# propulsion_alim.net
KiCad netlist of a schematic drawn in Altium Designer
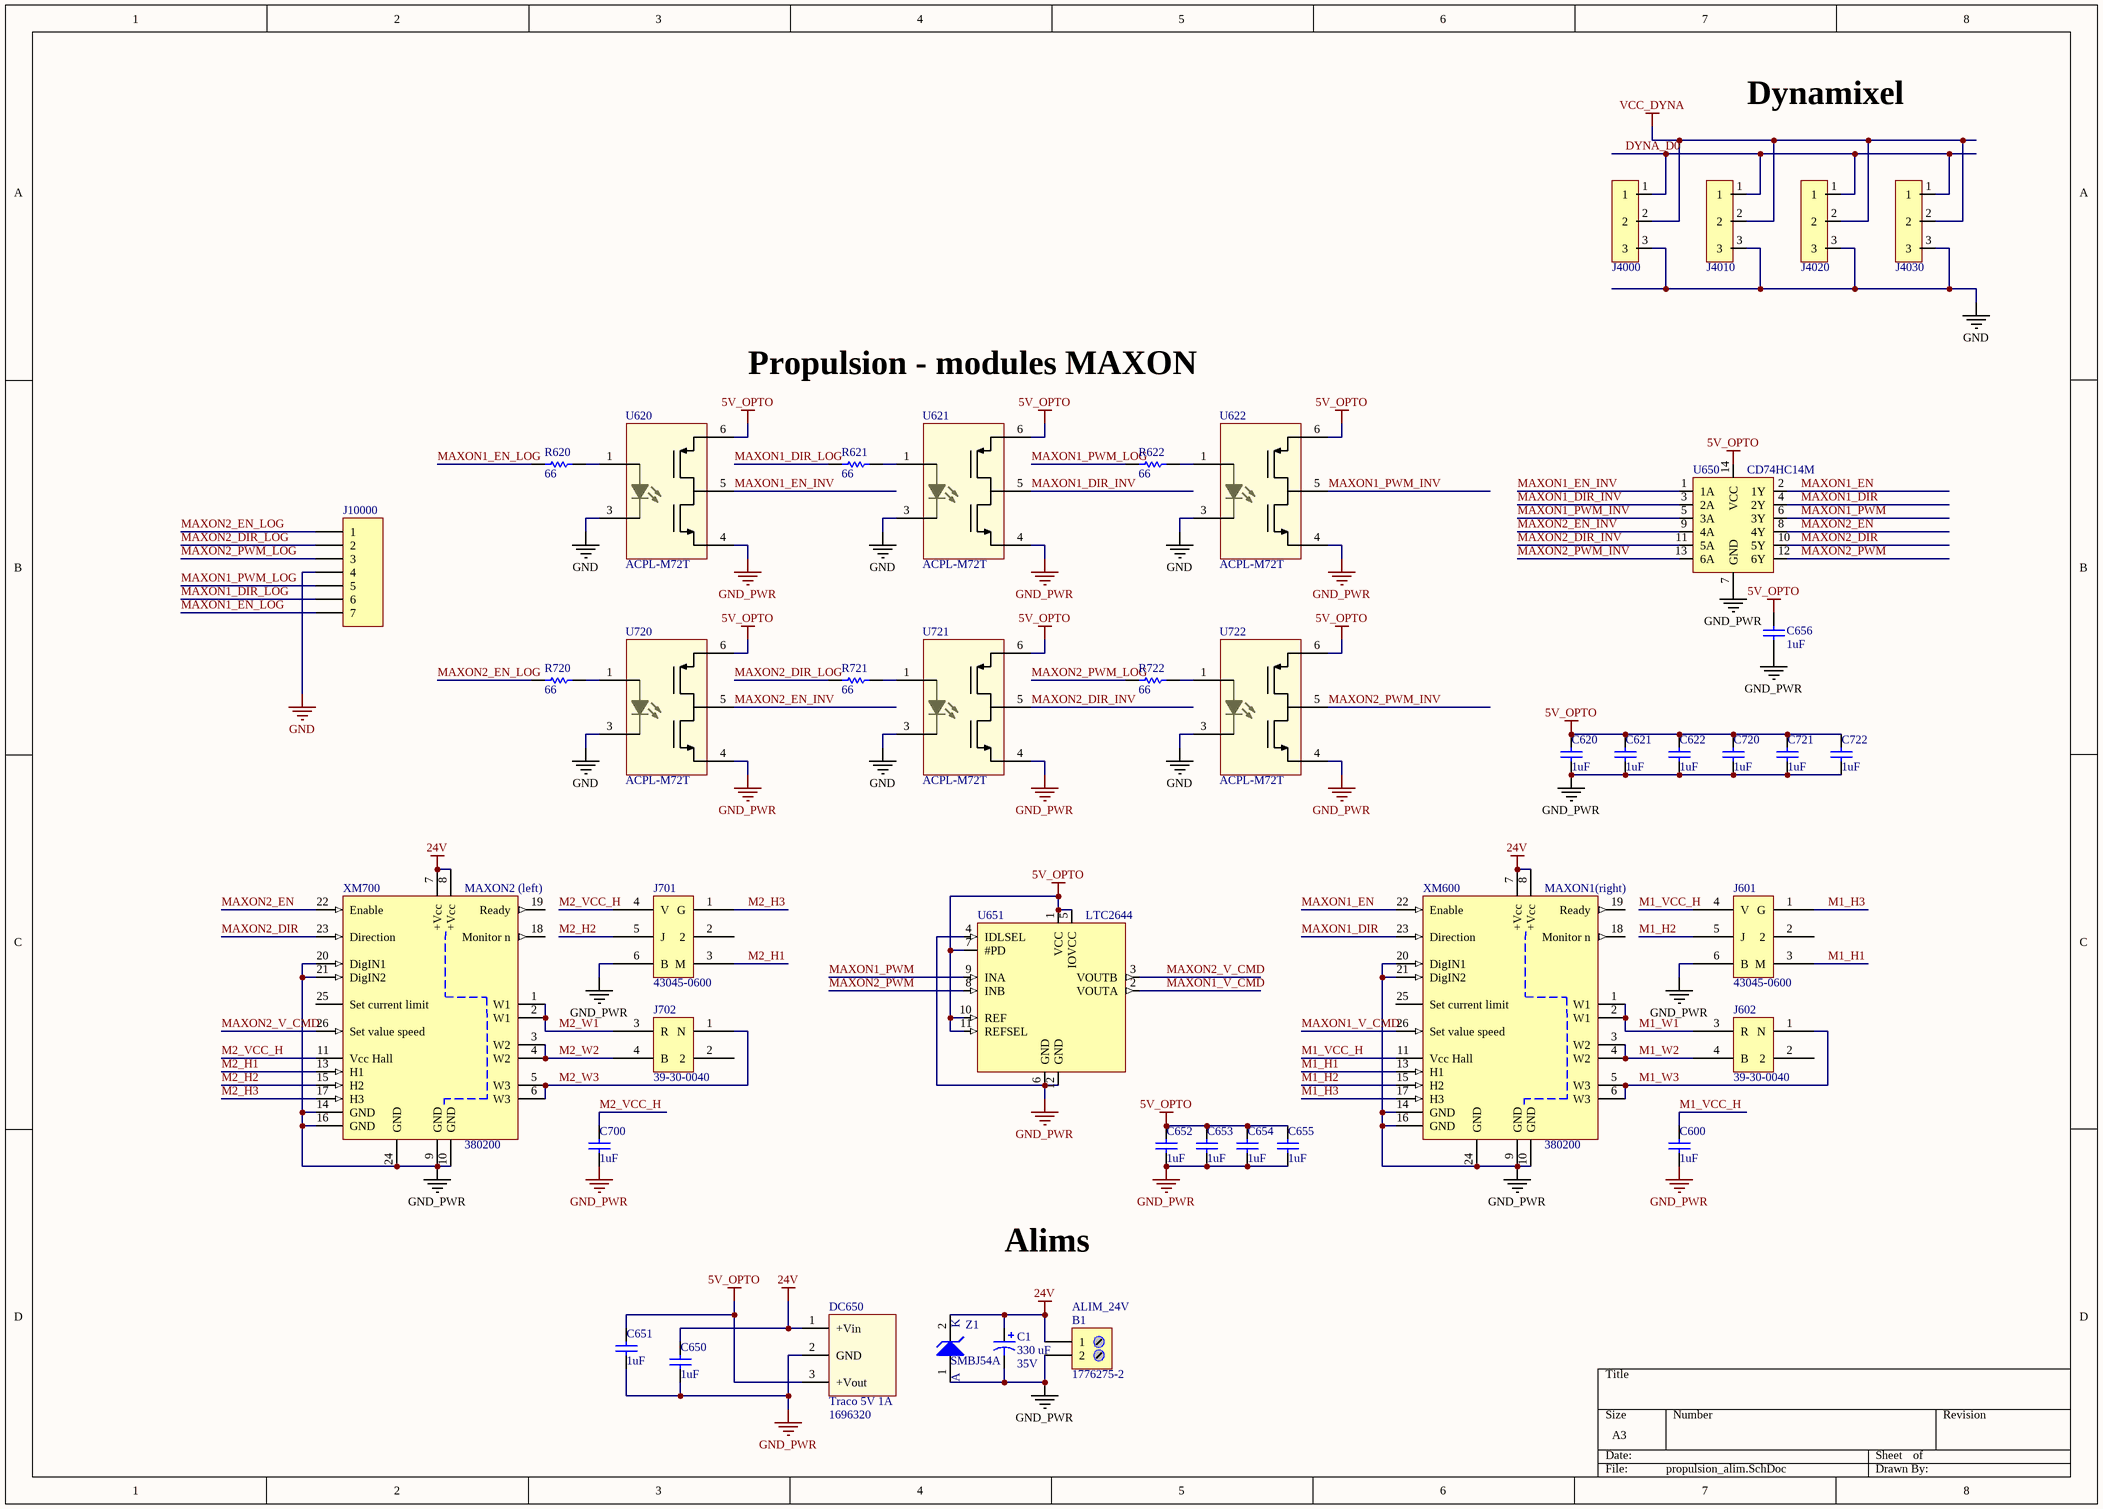
[diagram p0: propulsion_alim.SchDoc]

(export (version "E")
  (design (tool "Eeschema 10.0.6"))
  (components
    (comp (ref "B1")
      (value "1776275-2")
      (footprint "BORNIER_2V_3.5MM")
      (description "TERM BLOCK 2POS SIDE ENT 3.5MM")
      (fields (field (name "MANUFACTURER") "TE Connectivity AMP Connectors"))
      (libsource (lib "Divers") (part "1776275-2"))
    )
    (comp (ref "C1")
      (value "330 uF")
      (footprint "WCAP-ATG8_10x12.5x5x0.6")
      (description "CAP Alu 330 UF 20% 35 V")
      (fields
        (field (name "MANUFACTURER") "Wurth Elektronik")
        (field (name "MANUFACTURER PART NUMBER") "860010575012")
        (field (name "RATEDVOLTAGE") "35V")
      )
      (libsource (lib "Condensateur") (part "WCAP-ATG8, 860010575012"))
    )
    (comp (ref "C600")
      (value "1uF")
      (footprint "WCAP-CSGP_0805, 2x1.25x1.25")
      (description "CAP CER 1uF 50V X7R 0805")
      (fields
        (field (name "MANUFACTURER") "Wurth Elektronik")
        (field (name "MANUFACTURER PART NUMBER") "885012207103")
      )
      (libsource (lib "Condensateur") (part "WCAP-CSGP, 885012207103"))
    )
    (comp (ref "C620")
      (value "1uF")
      (footprint "WCAP-CSGP_0805, 2x1.25x1.25")
      (description "CAP CER 1uF 50V X7R 0805")
      (fields
        (field (name "MANUFACTURER") "Wurth Elektronik")
        (field (name "MANUFACTURER PART NUMBER") "885012207103")
      )
      (libsource (lib "Condensateur") (part "WCAP-CSGP, 885012207103"))
    )
    (comp (ref "C621")
      (value "1uF")
      (footprint "WCAP-CSGP_0805, 2x1.25x1.25")
      (description "CAP CER 1uF 50V X7R 0805")
      (fields
        (field (name "MANUFACTURER") "Wurth Elektronik")
        (field (name "MANUFACTURER PART NUMBER") "885012207103")
      )
      (libsource (lib "Condensateur") (part "WCAP-CSGP, 885012207103"))
    )
    (comp (ref "C622")
      (value "1uF")
      (footprint "WCAP-CSGP_0805, 2x1.25x1.25")
      (description "CAP CER 1uF 50V X7R 0805")
      (fields
        (field (name "MANUFACTURER") "Wurth Elektronik")
        (field (name "MANUFACTURER PART NUMBER") "885012207103")
      )
      (libsource (lib "Condensateur") (part "WCAP-CSGP, 885012207103"))
    )
    (comp (ref "C650")
      (value "1uF")
      (footprint "WCAP-CSGP_0805, 2x1.25x1.25")
      (description "CAP CER 1uF 50V X7R 0805")
      (fields
        (field (name "MANUFACTURER") "Wurth Elektronik")
        (field (name "MANUFACTURER PART NUMBER") "885012207103")
      )
      (libsource (lib "Condensateur") (part "WCAP-CSGP, 885012207103"))
    )
    (comp (ref "C651")
      (value "1uF")
      (footprint "WCAP-CSGP_0805, 2x1.25x1.25")
      (description "CAP CER 1uF 50V X7R 0805")
      (fields
        (field (name "MANUFACTURER") "Wurth Elektronik")
        (field (name "MANUFACTURER PART NUMBER") "885012207103")
      )
      (libsource (lib "Condensateur") (part "WCAP-CSGP, 885012207103"))
    )
    (comp (ref "C652")
      (value "1uF")
      (footprint "WCAP-CSGP_0805, 2x1.25x1.25")
      (description "CAP CER 1uF 50V X7R 0805")
      (fields
        (field (name "MANUFACTURER") "Wurth Elektronik")
        (field (name "MANUFACTURER PART NUMBER") "885012207103")
      )
      (libsource (lib "Condensateur") (part "WCAP-CSGP, 885012207103"))
    )
    (comp (ref "C653")
      (value "1uF")
      (footprint "WCAP-CSGP_0805, 2x1.25x1.25")
      (description "CAP CER 1uF 50V X7R 0805")
      (fields
        (field (name "MANUFACTURER") "Wurth Elektronik")
        (field (name "MANUFACTURER PART NUMBER") "885012207103")
      )
      (libsource (lib "Condensateur") (part "WCAP-CSGP, 885012207103"))
    )
    (comp (ref "C654")
      (value "1uF")
      (footprint "WCAP-CSGP_0805, 2x1.25x1.25")
      (description "CAP CER 1uF 50V X7R 0805")
      (fields
        (field (name "MANUFACTURER") "Wurth Elektronik")
        (field (name "MANUFACTURER PART NUMBER") "885012207103")
      )
      (libsource (lib "Condensateur") (part "WCAP-CSGP, 885012207103"))
    )
    (comp (ref "C655")
      (value "1uF")
      (footprint "WCAP-CSGP_0805, 2x1.25x1.25")
      (description "CAP CER 1uF 50V X7R 0805")
      (fields
        (field (name "MANUFACTURER") "Wurth Elektronik")
        (field (name "MANUFACTURER PART NUMBER") "885012207103")
      )
      (libsource (lib "Condensateur") (part "WCAP-CSGP, 885012207103"))
    )
    (comp (ref "C656")
      (value "1uF")
      (footprint "WCAP-CSGP_0805, 2x1.25x1.25")
      (description "CAP CER 1uF 50V X7R 0805")
      (fields
        (field (name "MANUFACTURER") "Wurth Elektronik")
        (field (name "MANUFACTURER PART NUMBER") "885012207103")
      )
      (libsource (lib "Condensateur") (part "WCAP-CSGP, 885012207103"))
    )
    (comp (ref "C700")
      (value "1uF")
      (footprint "WCAP-CSGP_0805, 2x1.25x1.25")
      (description "CAP CER 1uF 50V X7R 0805")
      (fields
        (field (name "MANUFACTURER") "Wurth Elektronik")
        (field (name "MANUFACTURER PART NUMBER") "885012207103")
      )
      (libsource (lib "Condensateur") (part "WCAP-CSGP, 885012207103"))
    )
    (comp (ref "C720")
      (value "1uF")
      (footprint "WCAP-CSGP_0805, 2x1.25x1.25")
      (description "CAP CER 1uF 50V X7R 0805")
      (fields
        (field (name "MANUFACTURER") "Wurth Elektronik")
        (field (name "MANUFACTURER PART NUMBER") "885012207103")
      )
      (libsource (lib "Condensateur") (part "WCAP-CSGP, 885012207103"))
    )
    (comp (ref "C721")
      (value "1uF")
      (footprint "WCAP-CSGP_0805, 2x1.25x1.25")
      (description "CAP CER 1uF 50V X7R 0805")
      (fields
        (field (name "MANUFACTURER") "Wurth Elektronik")
        (field (name "MANUFACTURER PART NUMBER") "885012207103")
      )
      (libsource (lib "Condensateur") (part "WCAP-CSGP, 885012207103"))
    )
    (comp (ref "C722")
      (value "1uF")
      (footprint "WCAP-CSGP_0805, 2x1.25x1.25")
      (description "CAP CER 1uF 50V X7R 0805")
      (fields
        (field (name "MANUFACTURER") "Wurth Elektronik")
        (field (name "MANUFACTURER PART NUMBER") "885012207103")
      )
      (libsource (lib "Condensateur") (part "WCAP-CSGP, 885012207103"))
    )
    (comp (ref "DC650")
      (value "Traco 5V 1A")
      (footprint "TSR1")
      (description "Traco 12.0V 12W 1A")
      (fields
        (field (name "MANUFACTURER") "TRACOPOWER")
        (field (name "MANUFACTURER PART NUMBER") "TSR1-2450")
        (field (name "SUPPLIER PART NUMBER 1") "1696320")
      )
      (libsource (lib "Alimentation") (part "TSR1-24120"))
    )
    (comp (ref "J601")
      (value "43045-0600")
      (footprint "Molex:43045-0600")
      (description "CONN HEADER 6POS 3MM RT ANG TIN")
      (fields (field (name "MANUFACTURER") "MOLEX"))
      (libsource (lib "Connecteurs") (part "43045-0600"))
    )
    (comp (ref "J602")
      (value "39-30-0040")
      (footprint "Molex:39-30-0040")
      (description "MOLEX  39-30-0040 4.2 mm, 4 Contact(s)")
      (fields (field (name "MANUFACTURER") "MOLEX"))
      (libsource (lib "Connecteurs") (part "39-30-0040"))
    )
    (comp (ref "J701")
      (value "43045-0600")
      (footprint "Molex:43045-0600")
      (description "CONN HEADER 6POS 3MM RT ANG TIN")
      (fields (field (name "MANUFACTURER") "MOLEX"))
      (libsource (lib "Connecteurs") (part "43045-0600"))
    )
    (comp (ref "J702")
      (value "39-30-0040")
      (footprint "Molex:39-30-0040")
      (description "MOLEX  39-30-0040 4.2 mm, 4 Contact(s)")
      (fields (field (name "MANUFACTURER") "MOLEX"))
      (libsource (lib "Connecteurs") (part "39-30-0040"))
    )
    (comp (ref "J4000")
      (value "22-03-5035")
      (footprint "20-03-5035")
      (libsource (lib "Connecteurs") (part "20-03-5035"))
    )
    (comp (ref "J4010")
      (value "22-03-5035")
      (footprint "20-03-5035")
      (libsource (lib "Connecteurs") (part "20-03-5035"))
    )
    (comp (ref "J4020")
      (value "22-03-5035")
      (footprint "20-03-5035")
      (libsource (lib "Connecteurs") (part "20-03-5035"))
    )
    (comp (ref "J4030")
      (value "22-03-5035")
      (footprint "20-03-5035")
      (libsource (lib "Connecteurs") (part "20-03-5035"))
    )
    (comp (ref "J10000")
      (value "~")
      (footprint "HDR1X7")
      (description "CONN HEADER 7POS 100MILS")
      (libsource (lib "Divers_goldo") (part "HDR1X7"))
    )
    (comp (ref "R620")
      (value "66")
      (footprint "RESC1608X06N")
      (description "RES SMD 10K OHM 1% 1/10W 0603")
      (fields
        (field (name "MANUFACTURER") "Yageo")
        (field (name "MANUFACTURER PART NUMBER") "RC0603FR-0710KL")
      )
      (libsource (lib "Resistance") (part "RC0603FR-0710KL"))
    )
    (comp (ref "R621")
      (value "66")
      (footprint "RESC1608X06N")
      (description "RES SMD 10K OHM 1% 1/10W 0603")
      (fields
        (field (name "MANUFACTURER") "Yageo")
        (field (name "MANUFACTURER PART NUMBER") "RC0603FR-0710KL")
      )
      (libsource (lib "Resistance") (part "RC0603FR-0710KL"))
    )
    (comp (ref "R622")
      (value "66")
      (footprint "RESC1608X06N")
      (description "RES SMD 10K OHM 1% 1/10W 0603")
      (fields
        (field (name "MANUFACTURER") "Yageo")
        (field (name "MANUFACTURER PART NUMBER") "RC0603FR-0710KL")
      )
      (libsource (lib "Resistance") (part "RC0603FR-0710KL"))
    )
    (comp (ref "R720")
      (value "66")
      (footprint "RESC1608X06N")
      (description "RES SMD 10K OHM 1% 1/10W 0603")
      (fields
        (field (name "MANUFACTURER") "Yageo")
        (field (name "MANUFACTURER PART NUMBER") "RC0603FR-0710KL")
      )
      (libsource (lib "Resistance") (part "RC0603FR-0710KL"))
    )
    (comp (ref "R721")
      (value "66")
      (footprint "RESC1608X06N")
      (description "RES SMD 10K OHM 1% 1/10W 0603")
      (fields
        (field (name "MANUFACTURER") "Yageo")
        (field (name "MANUFACTURER PART NUMBER") "RC0603FR-0710KL")
      )
      (libsource (lib "Resistance") (part "RC0603FR-0710KL"))
    )
    (comp (ref "R722")
      (value "66")
      (footprint "RESC1608X06N")
      (description "RES SMD 10K OHM 1% 1/10W 0603")
      (fields
        (field (name "MANUFACTURER") "Yageo")
        (field (name "MANUFACTURER PART NUMBER") "RC0603FR-0710KL")
      )
      (libsource (lib "Resistance") (part "RC0603FR-0710KL"))
    )
    (comp (ref "U620")
      (value "ACPL-M72T")
      (footprint "ACPL-M72T")
      (description "Optocoupleur")
      (fields (field (name "MANUFACTURER") "AVAGO TECHNOLOGIES"))
      (libsource (lib "Optoélectronique") (part "ACPL-M72T"))
    )
    (comp (ref "U621")
      (value "ACPL-M72T")
      (footprint "ACPL-M72T")
      (description "Optocoupleur")
      (fields (field (name "MANUFACTURER") "AVAGO TECHNOLOGIES"))
      (libsource (lib "Optoélectronique") (part "ACPL-M72T"))
    )
    (comp (ref "U622")
      (value "ACPL-M72T")
      (footprint "ACPL-M72T")
      (description "Optocoupleur")
      (fields (field (name "MANUFACTURER") "AVAGO TECHNOLOGIES"))
      (libsource (lib "Optoélectronique") (part "ACPL-M72T"))
    )
    (comp (ref "U650")
      (value "CD74HC14M")
      (footprint "SOIC127P600X175-14N")
      (description "IC HEX INV SCHMITT TRIG 14-SOIC")
      (fields (field (name "MANUFACTURER") "Texas Instruments"))
      (libsource (lib "Logique") (part "CD74HC14M"))
    )
    (comp (ref "U651")
      (value "LTC2644")
      (footprint "MSOP-12_LTC2644")
      (libsource (lib "CI") (part "LTC2644"))
    )
    (comp (ref "U720")
      (value "ACPL-M72T")
      (footprint "ACPL-M72T")
      (description "Optocoupleur")
      (fields (field (name "MANUFACTURER") "AVAGO TECHNOLOGIES"))
      (libsource (lib "Optoélectronique") (part "ACPL-M72T"))
    )
    (comp (ref "U721")
      (value "ACPL-M72T")
      (footprint "ACPL-M72T")
      (description "Optocoupleur")
      (fields (field (name "MANUFACTURER") "AVAGO TECHNOLOGIES"))
      (libsource (lib "Optoélectronique") (part "ACPL-M72T"))
    )
    (comp (ref "U722")
      (value "ACPL-M72T")
      (footprint "ACPL-M72T")
      (description "Optocoupleur")
      (fields (field (name "MANUFACTURER") "AVAGO TECHNOLOGIES"))
      (libsource (lib "Optoélectronique") (part "ACPL-M72T"))
    )
    (comp (ref "XM600")
      (value "380200")
      (footprint "380200_goldo")
      (description "DEC Module 50/5, amplificateur EC 1 Q 50 V / 5 A, régulation de vitesse, module OEM")
      (fields (field (name "MANUFACTURER") "Maxon Motor"))
      (libsource (lib "Divers") (part "380200"))
    )
    (comp (ref "XM700")
      (value "380200")
      (footprint "380200_goldo")
      (description "DEC Module 50/5, amplificateur EC 1 Q 50 V / 5 A, régulation de vitesse, module OEM")
      (fields (field (name "MANUFACTURER") "Maxon Motor"))
      (libsource (lib "Divers") (part "380200"))
    )
    (comp (ref "Z1")
      (value "SMBJ54A")
      (footprint "SMA Diode (DO-214AA)")
      (description "DIODE TVS (Transil unidirectionelle)")
      (fields (field (name "MANUFACTURER") "ON Semiconductor"))
      (libsource (lib "Redressement_goldo") (part "SMBJ54A"))
    )
  )
  (nets
    (net (code "1") (name "/DYNA_D0") (class "Default")
      (node (ref "J4000") (pin "1") (pinfunction "1_1") (pintype "passive"))
      (node (ref "J4010") (pin "1") (pinfunction "1_1") (pintype "passive"))
      (node (ref "J4020") (pin "1") (pinfunction "1_1") (pintype "passive"))
      (node (ref "J4030") (pin "1") (pinfunction "1_1") (pintype "passive"))
    )
    (net (code "2") (name "/M1_H1") (class "Default")
      (node (ref "J601") (pin "3") (pinfunction "M_3") (pintype "passive"))
      (node (ref "XM600") (pin "13") (pinfunction "H1_13") (pintype "input"))
    )
    (net (code "3") (name "/M1_H2") (class "Default")
      (node (ref "J601") (pin "5") (pinfunction "J_5") (pintype "passive"))
      (node (ref "XM600") (pin "15") (pinfunction "H2_15") (pintype "input"))
    )
    (net (code "4") (name "/M1_H3") (class "Default")
      (node (ref "J601") (pin "1") (pinfunction "G_1") (pintype "passive"))
      (node (ref "XM600") (pin "17") (pinfunction "H3_17") (pintype "input"))
    )
    (net (code "5") (name "/M1_VCC_H") (class "Default")
      (node (ref "C600") (pin "2") (pinfunction "2_2") (pintype "passive"))
      (node (ref "J601") (pin "4") (pinfunction "V_4") (pintype "passive"))
      (node (ref "XM600") (pin "11") (pinfunction "Vcc_Hall_11") (pintype "power_in"))
    )
    (net (code "6") (name "/M1_W1") (class "Default")
      (node (ref "J602") (pin "3") (pinfunction "R_3") (pintype "passive"))
      (node (ref "XM600") (pin "1") (pinfunction "W1_1") (pintype "passive"))
      (node (ref "XM600") (pin "2") (pinfunction "W1_2") (pintype "passive"))
    )
    (net (code "7") (name "/M1_W2") (class "Default")
      (node (ref "J602") (pin "4") (pinfunction "B_4") (pintype "passive"))
      (node (ref "XM600") (pin "3") (pinfunction "W2_3") (pintype "passive"))
      (node (ref "XM600") (pin "4") (pinfunction "W2_4") (pintype "passive"))
    )
    (net (code "8") (name "/M1_W3") (class "Default")
      (node (ref "J602") (pin "1") (pinfunction "N_1") (pintype "passive"))
      (node (ref "XM600") (pin "5") (pinfunction "W3_5") (pintype "passive"))
      (node (ref "XM600") (pin "6") (pinfunction "W3_6") (pintype "passive"))
    )
    (net (code "9") (name "/M2_H1") (class "Default")
      (node (ref "J701") (pin "3") (pinfunction "M_3") (pintype "passive"))
      (node (ref "XM700") (pin "13") (pinfunction "H1_13") (pintype "input"))
    )
    (net (code "10") (name "/M2_H2") (class "Default")
      (node (ref "J701") (pin "5") (pinfunction "J_5") (pintype "passive"))
      (node (ref "XM700") (pin "15") (pinfunction "H2_15") (pintype "input"))
    )
    (net (code "11") (name "/M2_H3") (class "Default")
      (node (ref "J701") (pin "1") (pinfunction "G_1") (pintype "passive"))
      (node (ref "XM700") (pin "17") (pinfunction "H3_17") (pintype "input"))
    )
    (net (code "12") (name "/M2_VCC_H") (class "Default")
      (node (ref "C700") (pin "2") (pinfunction "2_2") (pintype "passive"))
      (node (ref "J701") (pin "4") (pinfunction "V_4") (pintype "passive"))
      (node (ref "XM700") (pin "11") (pinfunction "Vcc_Hall_11") (pintype "power_in"))
    )
    (net (code "13") (name "/M2_W1") (class "Default")
      (node (ref "J702") (pin "3") (pinfunction "R_3") (pintype "passive"))
      (node (ref "XM700") (pin "1") (pinfunction "W1_1") (pintype "passive"))
      (node (ref "XM700") (pin "2") (pinfunction "W1_2") (pintype "passive"))
    )
    (net (code "14") (name "/M2_W2") (class "Default")
      (node (ref "J702") (pin "4") (pinfunction "B_4") (pintype "passive"))
      (node (ref "XM700") (pin "3") (pinfunction "W2_3") (pintype "passive"))
      (node (ref "XM700") (pin "4") (pinfunction "W2_4") (pintype "passive"))
    )
    (net (code "15") (name "/M2_W3") (class "Default")
      (node (ref "J702") (pin "1") (pinfunction "N_1") (pintype "passive"))
      (node (ref "XM700") (pin "5") (pinfunction "W3_5") (pintype "passive"))
      (node (ref "XM700") (pin "6") (pinfunction "W3_6") (pintype "passive"))
    )
    (net (code "16") (name "/MAXON1_DIR") (class "Default")
      (node (ref "U650") (pin "4") (pinfunction "2Y_4") (pintype "passive"))
      (node (ref "XM600") (pin "23") (pinfunction "Direction_23") (pintype "input"))
    )
    (net (code "17") (name "/MAXON1_DIR_INV") (class "Default")
      (node (ref "U621") (pin "5") (pinfunction "Vo_5") (pintype "passive"))
      (node (ref "U650") (pin "3") (pinfunction "2A_3") (pintype "passive"))
    )
    (net (code "18") (name "/MAXON1_DIR_LOG") (class "Default")
      (node (ref "J10000") (pin "6") (pinfunction "6_6") (pintype "passive"))
      (node (ref "R621") (pin "1") (pinfunction "1_1") (pintype "passive"))
    )
    (net (code "19") (name "/MAXON1_EN") (class "Default")
      (node (ref "U650") (pin "2") (pinfunction "1Y_2") (pintype "passive"))
      (node (ref "XM600") (pin "22") (pinfunction "Enable_22") (pintype "input"))
    )
    (net (code "20") (name "/MAXON1_EN_INV") (class "Default")
      (node (ref "U620") (pin "5") (pinfunction "Vo_5") (pintype "passive"))
      (node (ref "U650") (pin "1") (pinfunction "1A_1") (pintype "passive"))
    )
    (net (code "21") (name "/MAXON1_EN_LOG") (class "Default")
      (node (ref "J10000") (pin "7") (pinfunction "7_7") (pintype "passive"))
      (node (ref "R620") (pin "1") (pinfunction "1_1") (pintype "passive"))
    )
    (net (code "22") (name "/MAXON1_PWM") (class "Default")
      (node (ref "U650") (pin "6") (pinfunction "3Y_6") (pintype "passive"))
      (node (ref "U651") (pin "9") (pinfunction "INA_9") (pintype "input"))
    )
    (net (code "23") (name "/MAXON1_PWM_INV") (class "Default")
      (node (ref "U622") (pin "5") (pinfunction "Vo_5") (pintype "passive"))
      (node (ref "U650") (pin "5") (pinfunction "3A_5") (pintype "passive"))
    )
    (net (code "24") (name "/MAXON1_PWM_LOG") (class "Default")
      (node (ref "J10000") (pin "5") (pinfunction "5_5") (pintype "passive"))
      (node (ref "R622") (pin "1") (pinfunction "1_1") (pintype "passive"))
    )
    (net (code "25") (name "/MAXON1_V_CMD") (class "Default")
      (node (ref "U651") (pin "2") (pinfunction "VOUTA_2") (pintype "output"))
      (node (ref "XM600") (pin "26") (pinfunction "Set_value_speed_26") (pintype "input"))
    )
    (net (code "26") (name "/MAXON2_DIR") (class "Default")
      (node (ref "U650") (pin "10") (pinfunction "5Y_10") (pintype "passive"))
      (node (ref "XM700") (pin "23") (pinfunction "Direction_23") (pintype "input"))
    )
    (net (code "27") (name "/MAXON2_DIR_INV") (class "Default")
      (node (ref "U650") (pin "11") (pinfunction "5A_11") (pintype "passive"))
      (node (ref "U721") (pin "5") (pinfunction "Vo_5") (pintype "passive"))
    )
    (net (code "28") (name "/MAXON2_DIR_LOG") (class "Default")
      (node (ref "J10000") (pin "2") (pinfunction "2_2") (pintype "passive"))
      (node (ref "R721") (pin "1") (pinfunction "1_1") (pintype "passive"))
    )
    (net (code "29") (name "/MAXON2_EN") (class "Default")
      (node (ref "U650") (pin "8") (pinfunction "4Y_8") (pintype "passive"))
      (node (ref "XM700") (pin "22") (pinfunction "Enable_22") (pintype "input"))
    )
    (net (code "30") (name "/MAXON2_EN_INV") (class "Default")
      (node (ref "U650") (pin "9") (pinfunction "4A_9") (pintype "passive"))
      (node (ref "U720") (pin "5") (pinfunction "Vo_5") (pintype "passive"))
    )
    (net (code "31") (name "/MAXON2_EN_LOG") (class "Default")
      (node (ref "J10000") (pin "1") (pinfunction "1_1") (pintype "passive"))
      (node (ref "R720") (pin "1") (pinfunction "1_1") (pintype "passive"))
    )
    (net (code "32") (name "/MAXON2_PWM") (class "Default")
      (node (ref "U650") (pin "12") (pinfunction "6Y_12") (pintype "passive"))
      (node (ref "U651") (pin "8") (pinfunction "INB_8") (pintype "input"))
    )
    (net (code "33") (name "/MAXON2_PWM_INV") (class "Default")
      (node (ref "U650") (pin "13") (pinfunction "6A_13") (pintype "passive"))
      (node (ref "U722") (pin "5") (pinfunction "Vo_5") (pintype "passive"))
    )
    (net (code "34") (name "/MAXON2_PWM_LOG") (class "Default")
      (node (ref "J10000") (pin "3") (pinfunction "3_3") (pintype "passive"))
      (node (ref "R722") (pin "1") (pinfunction "1_1") (pintype "passive"))
    )
    (net (code "35") (name "/MAXON2_V_CMD") (class "Default")
      (node (ref "U651") (pin "3") (pinfunction "VOUTB_3") (pintype "output"))
      (node (ref "XM700") (pin "26") (pinfunction "Set_value_speed_26") (pintype "input"))
    )
    (net (code "36") (name "5V_OPTO") (class "Default")
      (node (ref "C620") (pin "2") (pinfunction "2_2") (pintype "passive"))
      (node (ref "C621") (pin "2") (pinfunction "2_2") (pintype "passive"))
      (node (ref "C622") (pin "2") (pinfunction "2_2") (pintype "passive"))
      (node (ref "C651") (pin "2") (pinfunction "2_2") (pintype "passive"))
      (node (ref "C652") (pin "2") (pinfunction "2_2") (pintype "passive"))
      (node (ref "C653") (pin "2") (pinfunction "2_2") (pintype "passive"))
      (node (ref "C654") (pin "2") (pinfunction "2_2") (pintype "passive"))
      (node (ref "C655") (pin "2") (pinfunction "2_2") (pintype "passive"))
      (node (ref "C656") (pin "2") (pinfunction "2_2") (pintype "passive"))
      (node (ref "C720") (pin "2") (pinfunction "2_2") (pintype "passive"))
      (node (ref "C721") (pin "2") (pinfunction "2_2") (pintype "passive"))
      (node (ref "C722") (pin "2") (pinfunction "2_2") (pintype "passive"))
      (node (ref "DC650") (pin "3") (pinfunction "+Vout_3") (pintype "power_in"))
      (node (ref "U620") (pin "6") (pinfunction "VDD_6") (pintype "passive"))
      (node (ref "U621") (pin "6") (pinfunction "VDD_6") (pintype "passive"))
      (node (ref "U622") (pin "6") (pinfunction "VDD_6") (pintype "passive"))
      (node (ref "U650") (pin "14") (pinfunction "VCC_14") (pintype "passive"))
      (node (ref "U651") (pin "1") (pinfunction "VCC_1") (pintype "power_in"))
      (node (ref "U651") (pin "10") (pinfunction "REF_10") (pintype "input"))
      (node (ref "U651") (pin "11") (pinfunction "REFSEL_11") (pintype "input"))
      (node (ref "U651") (pin "5") (pinfunction "IOVCC_5") (pintype "power_in"))
      (node (ref "U651") (pin "7") (pinfunction "#PD_7") (pintype "passive"))
      (node (ref "U720") (pin "6") (pinfunction "VDD_6") (pintype "passive"))
      (node (ref "U721") (pin "6") (pinfunction "VDD_6") (pintype "passive"))
      (node (ref "U722") (pin "6") (pinfunction "VDD_6") (pintype "passive"))
    )
    (net (code "37") (name "24V") (class "Default")
      (node (ref "B1") (pin "1") (pinfunction "1_1") (pintype "passive"))
      (node (ref "C1") (pin "1") (pinfunction "1_1") (pintype "passive"))
      (node (ref "C650") (pin "2") (pinfunction "2_2") (pintype "passive"))
      (node (ref "DC650") (pin "1") (pinfunction "+Vin_1") (pintype "power_in"))
      (node (ref "XM600") (pin "7") (pinfunction "+Vcc_7") (pintype "power_in"))
      (node (ref "XM600") (pin "8") (pinfunction "+Vcc_8") (pintype "power_in"))
      (node (ref "XM700") (pin "7") (pinfunction "+Vcc_7") (pintype "power_in"))
      (node (ref "XM700") (pin "8") (pinfunction "+Vcc_8") (pintype "power_in"))
      (node (ref "Z1") (pin "2") (pintype "passive"))
    )
    (net (code "38") (name "GND") (class "Default")
      (node (ref "J10000") (pin "4") (pinfunction "4_4") (pintype "passive"))
      (node (ref "J4000") (pin "3") (pinfunction "3_3") (pintype "passive"))
      (node (ref "J4010") (pin "3") (pinfunction "3_3") (pintype "passive"))
      (node (ref "J4020") (pin "3") (pinfunction "3_3") (pintype "passive"))
      (node (ref "J4030") (pin "3") (pinfunction "3_3") (pintype "passive"))
      (node (ref "U620") (pin "3") (pinfunction "Cathode_3") (pintype "passive"))
      (node (ref "U621") (pin "3") (pinfunction "Cathode_3") (pintype "passive"))
      (node (ref "U622") (pin "3") (pinfunction "Cathode_3") (pintype "passive"))
      (node (ref "U720") (pin "3") (pinfunction "Cathode_3") (pintype "passive"))
      (node (ref "U721") (pin "3") (pinfunction "Cathode_3") (pintype "passive"))
      (node (ref "U722") (pin "3") (pinfunction "Cathode_3") (pintype "passive"))
    )
    (net (code "39") (name "GND_PWR") (class "Default")
      (node (ref "B1") (pin "2") (pinfunction "2_2") (pintype "passive"))
      (node (ref "C1") (pin "2") (pinfunction "2_2") (pintype "passive"))
      (node (ref "C600") (pin "1") (pinfunction "1_1") (pintype "passive"))
      (node (ref "C620") (pin "1") (pinfunction "1_1") (pintype "passive"))
      (node (ref "C621") (pin "1") (pinfunction "1_1") (pintype "passive"))
      (node (ref "C622") (pin "1") (pinfunction "1_1") (pintype "passive"))
      (node (ref "C650") (pin "1") (pinfunction "1_1") (pintype "passive"))
      (node (ref "C651") (pin "1") (pinfunction "1_1") (pintype "passive"))
      (node (ref "C652") (pin "1") (pinfunction "1_1") (pintype "passive"))
      (node (ref "C653") (pin "1") (pinfunction "1_1") (pintype "passive"))
      (node (ref "C654") (pin "1") (pinfunction "1_1") (pintype "passive"))
      (node (ref "C655") (pin "1") (pinfunction "1_1") (pintype "passive"))
      (node (ref "C656") (pin "1") (pinfunction "1_1") (pintype "passive"))
      (node (ref "C700") (pin "1") (pinfunction "1_1") (pintype "passive"))
      (node (ref "C720") (pin "1") (pinfunction "1_1") (pintype "passive"))
      (node (ref "C721") (pin "1") (pinfunction "1_1") (pintype "passive"))
      (node (ref "C722") (pin "1") (pinfunction "1_1") (pintype "passive"))
      (node (ref "DC650") (pin "2") (pinfunction "GND_2") (pintype "power_in"))
      (node (ref "J601") (pin "6") (pinfunction "B_6") (pintype "passive"))
      (node (ref "J701") (pin "6") (pinfunction "B_6") (pintype "passive"))
      (node (ref "U620") (pin "4") (pinfunction "GND_4") (pintype "passive"))
      (node (ref "U621") (pin "4") (pinfunction "GND_4") (pintype "passive"))
      (node (ref "U622") (pin "4") (pinfunction "GND_4") (pintype "passive"))
      (node (ref "U650") (pin "7") (pinfunction "GND_7") (pintype "passive"))
      (node (ref "U651") (pin "12") (pinfunction "GND_12") (pintype "power_in"))
      (node (ref "U651") (pin "4") (pinfunction "IDLSEL_4") (pintype "input"))
      (node (ref "U651") (pin "6") (pinfunction "GND_6") (pintype "power_in"))
      (node (ref "U720") (pin "4") (pinfunction "GND_4") (pintype "passive"))
      (node (ref "U721") (pin "4") (pinfunction "GND_4") (pintype "passive"))
      (node (ref "U722") (pin "4") (pinfunction "GND_4") (pintype "passive"))
      (node (ref "XM600") (pin "10") (pinfunction "GND_10") (pintype "power_in"))
      (node (ref "XM600") (pin "14") (pinfunction "GND_14") (pintype "power_in"))
      (node (ref "XM600") (pin "16") (pinfunction "GND_16") (pintype "power_in"))
      (node (ref "XM600") (pin "20") (pinfunction "DigIN1_20") (pintype "input"))
      (node (ref "XM600") (pin "21") (pinfunction "DigIN2_21") (pintype "input"))
      (node (ref "XM600") (pin "24") (pinfunction "GND_24") (pintype "power_in"))
      (node (ref "XM600") (pin "9") (pinfunction "GND_9") (pintype "power_in"))
      (node (ref "XM700") (pin "10") (pinfunction "GND_10") (pintype "power_in"))
      (node (ref "XM700") (pin "14") (pinfunction "GND_14") (pintype "power_in"))
      (node (ref "XM700") (pin "16") (pinfunction "GND_16") (pintype "power_in"))
      (node (ref "XM700") (pin "20") (pinfunction "DigIN1_20") (pintype "input"))
      (node (ref "XM700") (pin "21") (pinfunction "DigIN2_21") (pintype "input"))
      (node (ref "XM700") (pin "24") (pinfunction "GND_24") (pintype "power_in"))
      (node (ref "XM700") (pin "9") (pinfunction "GND_9") (pintype "power_in"))
      (node (ref "Z1") (pin "1") (pintype "passive"))
    )
    (net (code "40") (name "Net-(U620-Anode)") (class "Default")
      (node (ref "R620") (pin "2") (pinfunction "2_2") (pintype "passive"))
      (node (ref "U620") (pin "1") (pinfunction "Anode_1") (pintype "passive"))
    )
    (net (code "41") (name "Net-(U621-Anode)") (class "Default")
      (node (ref "R621") (pin "2") (pinfunction "2_2") (pintype "passive"))
      (node (ref "U621") (pin "1") (pinfunction "Anode_1") (pintype "passive"))
    )
    (net (code "42") (name "Net-(U622-Anode)") (class "Default")
      (node (ref "R622") (pin "2") (pinfunction "2_2") (pintype "passive"))
      (node (ref "U622") (pin "1") (pinfunction "Anode_1") (pintype "passive"))
    )
    (net (code "43") (name "Net-(U720-Anode)") (class "Default")
      (node (ref "R720") (pin "2") (pinfunction "2_2") (pintype "passive"))
      (node (ref "U720") (pin "1") (pinfunction "Anode_1") (pintype "passive"))
    )
    (net (code "44") (name "Net-(U721-Anode)") (class "Default")
      (node (ref "R721") (pin "2") (pinfunction "2_2") (pintype "passive"))
      (node (ref "U721") (pin "1") (pinfunction "Anode_1") (pintype "passive"))
    )
    (net (code "45") (name "Net-(U722-Anode)") (class "Default")
      (node (ref "R722") (pin "2") (pinfunction "2_2") (pintype "passive"))
      (node (ref "U722") (pin "1") (pinfunction "Anode_1") (pintype "passive"))
    )
    (net (code "46") (name "VCC_DYNA") (class "Default")
      (node (ref "J4000") (pin "2") (pinfunction "2_2") (pintype "passive"))
      (node (ref "J4010") (pin "2") (pinfunction "2_2") (pintype "passive"))
      (node (ref "J4020") (pin "2") (pinfunction "2_2") (pintype "passive"))
      (node (ref "J4030") (pin "2") (pinfunction "2_2") (pintype "passive"))
    )
    (net (code "47") (name "unconnected-(J601-Pad2)") (class "Default")
      (node (ref "J601") (pin "2") (pinfunction "2_2") (pintype "passive"))
    )
    (net (code "48") (name "unconnected-(J602-Pad2)") (class "Default")
      (node (ref "J602") (pin "2") (pinfunction "2_2") (pintype "passive"))
    )
    (net (code "49") (name "unconnected-(J701-Pad2)") (class "Default")
      (node (ref "J701") (pin "2") (pinfunction "2_2") (pintype "passive"))
    )
    (net (code "50") (name "unconnected-(J702-Pad2)") (class "Default")
      (node (ref "J702") (pin "2") (pinfunction "2_2") (pintype "passive"))
    )
    (net (code "51") (name "unconnected-(XM600-Monitor_n-Pad18)") (class "Default")
      (node (ref "XM600") (pin "18") (pinfunction "Monitor_n_18") (pintype "output"))
    )
    (net (code "52") (name "unconnected-(XM600-Ready-Pad19)") (class "Default")
      (node (ref "XM600") (pin "19") (pinfunction "Ready_19") (pintype "output"))
    )
    (net (code "53") (name "unconnected-(XM600-Set_current_limit-Pad25)") (class "Default")
      (node (ref "XM600") (pin "25") (pinfunction "Set_current_limit_25") (pintype "passive"))
    )
    (net (code "54") (name "unconnected-(XM600-nc-Pad12)") (class "Default")
      (node (ref "XM600") (pin "12") (pinfunction "nc_12") (pintype "passive"))
    )
    (net (code "55") (name "unconnected-(XM700-Monitor_n-Pad18)") (class "Default")
      (node (ref "XM700") (pin "18") (pinfunction "Monitor_n_18") (pintype "output"))
    )
    (net (code "56") (name "unconnected-(XM700-Ready-Pad19)") (class "Default")
      (node (ref "XM700") (pin "19") (pinfunction "Ready_19") (pintype "output"))
    )
    (net (code "57") (name "unconnected-(XM700-Set_current_limit-Pad25)") (class "Default")
      (node (ref "XM700") (pin "25") (pinfunction "Set_current_limit_25") (pintype "passive"))
    )
    (net (code "58") (name "unconnected-(XM700-nc-Pad12)") (class "Default")
      (node (ref "XM700") (pin "12") (pinfunction "nc_12") (pintype "passive"))
    )
  )
)
